# TC_IC1.net
KiCad netlist of a schematic drawn in Altium Designer
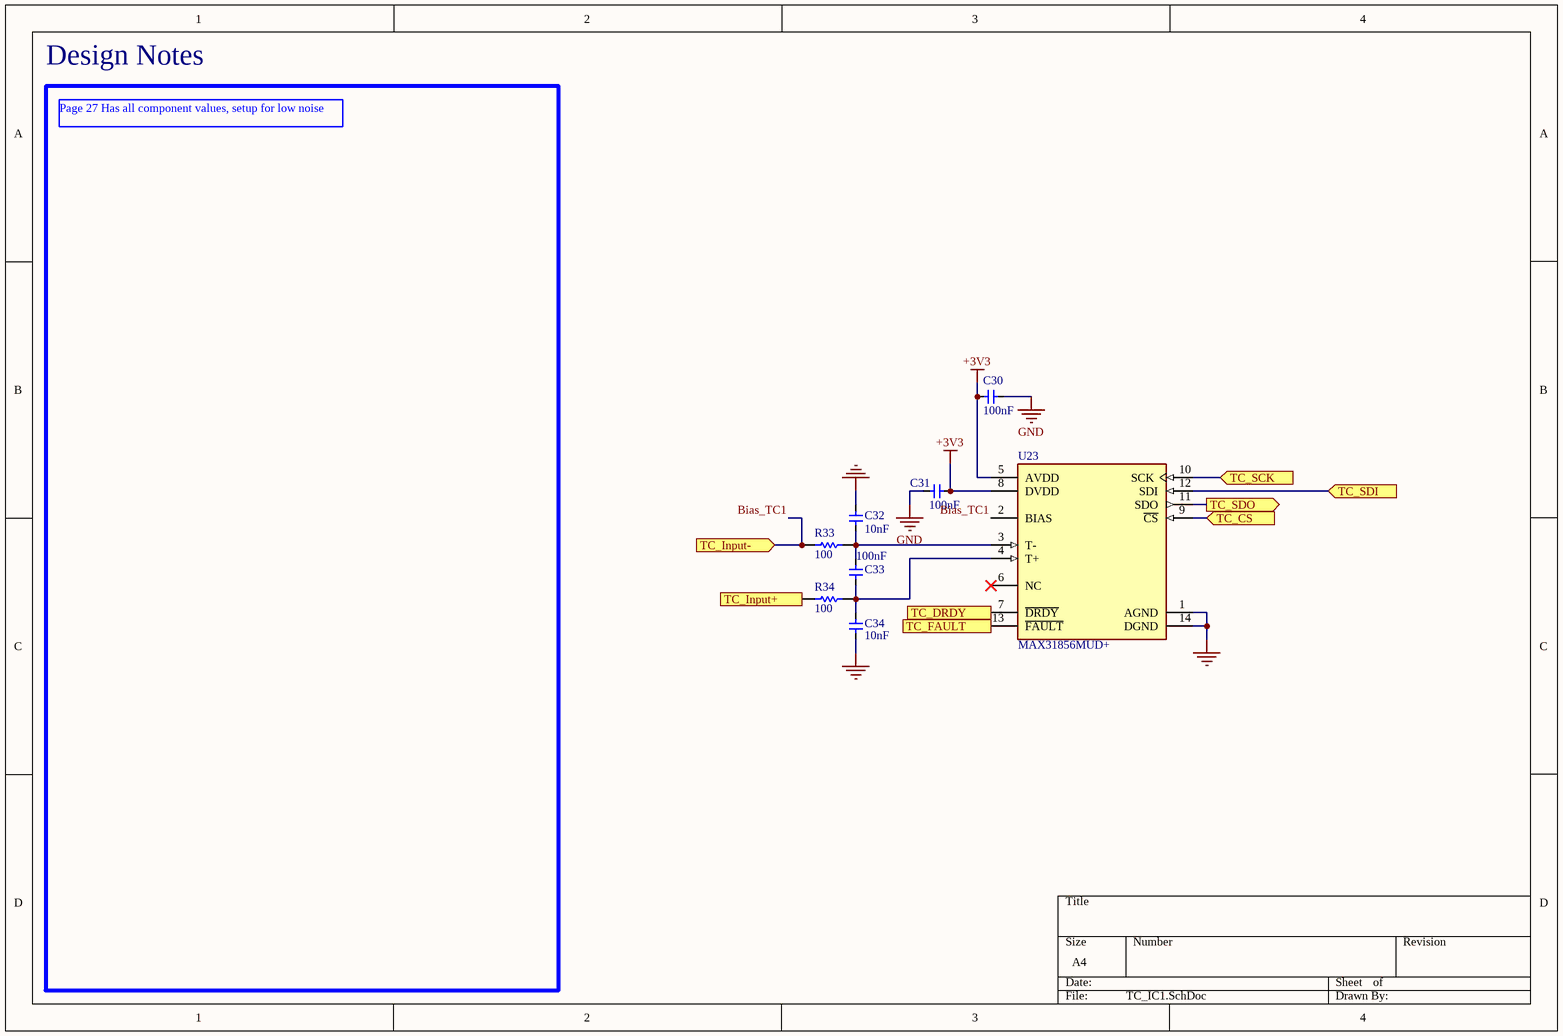
[diagram p0: TC_IC1.SchDoc]

(export (version "E")
  (design (tool "Eeschema 10.0.6"))
  (components
    (comp (ref "C30")
      (value "100nF")
      (footprint "0.1uF-FP-CGA3E-0_3-0_1-IPC_A")
      (description "CGA3E2X7R1E104K080AA CAP CER 0.1UF 25V X7R 0603")
      (fields
        (field (name "TOLERANCE") "10%")
        (field (name "MANUFACTURER") "TDK Corporation")
        (field (name "SOURCE") "PlumBay_SchLib.SchLib")
      )
      (libsource (lib "University of Calgary - SOAR") (part "100nF"))
    )
    (comp (ref "C31")
      (value "100nF")
      (footprint "0.1uF-FP-CGA3E-0_3-0_1-IPC_A")
      (description "CGA3E2X7R1E104K080AA CAP CER 0.1UF 25V X7R 0603")
      (fields
        (field (name "TOLERANCE") "10%")
        (field (name "MANUFACTURER") "TDK Corporation")
        (field (name "SOURCE") "PlumBay_SchLib.SchLib")
      )
      (libsource (lib "University of Calgary - SOAR") (part "100nF"))
    )
    (comp (ref "C32")
      (value "10nF")
      (footprint "10000pF-CAP_1608_TDK")
      (description "CAP CER 10000PF 50V X7R 0603")
      (fields
        (field (name "MANUFACTURER") "TDK Corporation")
        (field (name "TOLERANCE") "10%")
        (field (name "SOURCE") "PlumBay_SchLib.SchLib")
      )
      (libsource (lib "University of Calgary - SOAR") (part "CGA3E2X7R1H103K080AA"))
    )
    (comp (ref "C33")
      (value "100nF")
      (footprint "0.1uF-FP-CGA3E-0_3-0_1-IPC_A")
      (description "CGA3E2X7R1E104K080AA CAP CER 0.1UF 25V X7R 0603")
      (fields
        (field (name "TOLERANCE") "10%")
        (field (name "MANUFACTURER") "TDK Corporation")
        (field (name "SOURCE") "PlumBay_SchLib.SchLib")
      )
      (libsource (lib "University of Calgary - SOAR") (part "100nF"))
    )
    (comp (ref "C34")
      (value "10nF")
      (footprint "10000pF-CAP_1608_TDK")
      (description "CAP CER 10000PF 50V X7R 0603")
      (fields
        (field (name "MANUFACTURER") "TDK Corporation")
        (field (name "TOLERANCE") "10%")
        (field (name "SOURCE") "PlumBay_SchLib.SchLib")
      )
      (libsource (lib "University of Calgary - SOAR") (part "CGA3E2X7R1H103K080AA"))
    )
    (comp (ref "R33")
      (value "100")
      (footprint "RESC1608X55X30LL15T15")
      (fields
        (field (name "POWER") "100mW")
        (field (name "TOLERANCE") "1%")
        (field (name "Comment") "ERJ-3EKF1000V")
      )
      (libsource (lib "University of Calgary - SOAR") (part "RES"))
    )
    (comp (ref "R34")
      (value "100")
      (footprint "RESC1608X55X30LL15T15")
      (fields
        (field (name "POWER") "100mW")
        (field (name "TOLERANCE") "1%")
        (field (name "Comment") "ERJ-3EKF1000V")
      )
      (libsource (lib "University of Calgary - SOAR") (part "RES"))
    )
    (comp (ref "U23")
      (value "MAX31856MUD+")
      (footprint "FP-U14-2-MFG")
      (description "Analog Circuit, 1 Func, PDSO14")
      (libsource (lib "University of Calgary - SOAR") (part "746ee3d58a922cadd982a8de1b076a0"))
    )
  )
  (nets
    (net (code "1") (name "+3V3") (class "Default")
      (node (ref "C30") (pin "1") (pinfunction "1_1") (pintype "passive"))
      (node (ref "C31") (pin "1") (pinfunction "1_1") (pintype "passive"))
      (node (ref "U23") (pin "5") (pinfunction "AVDD_5") (pintype "power_in"))
      (node (ref "U23") (pin "8") (pinfunction "DVDD_8") (pintype "power_in"))
    )
    (net (code "2") (name "/Bias_TC1") (class "Default")
      (node (ref "R33") (pin "2") (pinfunction "2_2") (pintype "passive"))
      (node (ref "U23") (pin "2") (pinfunction "BIAS_2") (pintype "passive"))
    )
    (net (code "3") (name "/TC_CS") (class "Default")
      (node (ref "U23") (pin "9") (pinfunction "~{CS}_9") (pintype "input"))
    )
    (net (code "4") (name "/TC_DRDY") (class "Default")
      (node (ref "U23") (pin "7") (pinfunction "~{DRDY}_7") (pintype "passive"))
    )
    (net (code "5") (name "/TC_FAULT") (class "Default")
      (node (ref "U23") (pin "13") (pinfunction "~{FAULT}_13") (pintype "passive"))
    )
    (net (code "6") (name "/TC_Input+") (class "Default")
      (node (ref "R34") (pin "2") (pinfunction "2_2") (pintype "passive"))
    )
    (net (code "7") (name "/TC_SCK") (class "Default")
      (node (ref "U23") (pin "10") (pinfunction "SCK_10") (pintype "input"))
    )
    (net (code "8") (name "/TC_SDI") (class "Default")
      (node (ref "U23") (pin "12") (pinfunction "SDI_12") (pintype "input"))
    )
    (net (code "9") (name "/TC_SDO") (class "Default")
      (node (ref "U23") (pin "11") (pinfunction "SDO_11") (pintype "output"))
    )
    (net (code "10") (name "GND") (class "Default")
      (node (ref "C30") (pin "2") (pinfunction "2_2") (pintype "passive"))
      (node (ref "C31") (pin "2") (pinfunction "2_2") (pintype "passive"))
      (node (ref "C32") (pin "1") (pinfunction "1_1") (pintype "passive"))
      (node (ref "C34") (pin "1") (pinfunction "1_1") (pintype "passive"))
      (node (ref "U23") (pin "1") (pinfunction "AGND_1") (pintype "power_in"))
      (node (ref "U23") (pin "14") (pinfunction "DGND_14") (pintype "power_in"))
    )
    (net (code "11") (name "Net-(U23-T+)") (class "Default")
      (node (ref "C33") (pin "1") (pinfunction "1_1") (pintype "passive"))
      (node (ref "C34") (pin "2") (pinfunction "2_2") (pintype "passive"))
      (node (ref "R34") (pin "1") (pinfunction "1_1") (pintype "passive"))
      (node (ref "U23") (pin "4") (pinfunction "T+_4") (pintype "input"))
    )
    (net (code "12") (name "Net-(U23-T-)") (class "Default")
      (node (ref "C32") (pin "2") (pinfunction "2_2") (pintype "passive"))
      (node (ref "C33") (pin "2") (pinfunction "2_2") (pintype "passive"))
      (node (ref "R33") (pin "1") (pinfunction "1_1") (pintype "passive"))
      (node (ref "U23") (pin "3") (pinfunction "T-_3") (pintype "input"))
    )
    (net (code "13") (name "unconnected-(U23-NC-Pad6)") (class "Default")
      (node (ref "U23") (pin "6") (pinfunction "NC_6") (pintype "passive+no_connect"))
    )
  )
)
